# pixelAdapter_l432.net
KiCad netlist of a schematic drawn in EAGLE
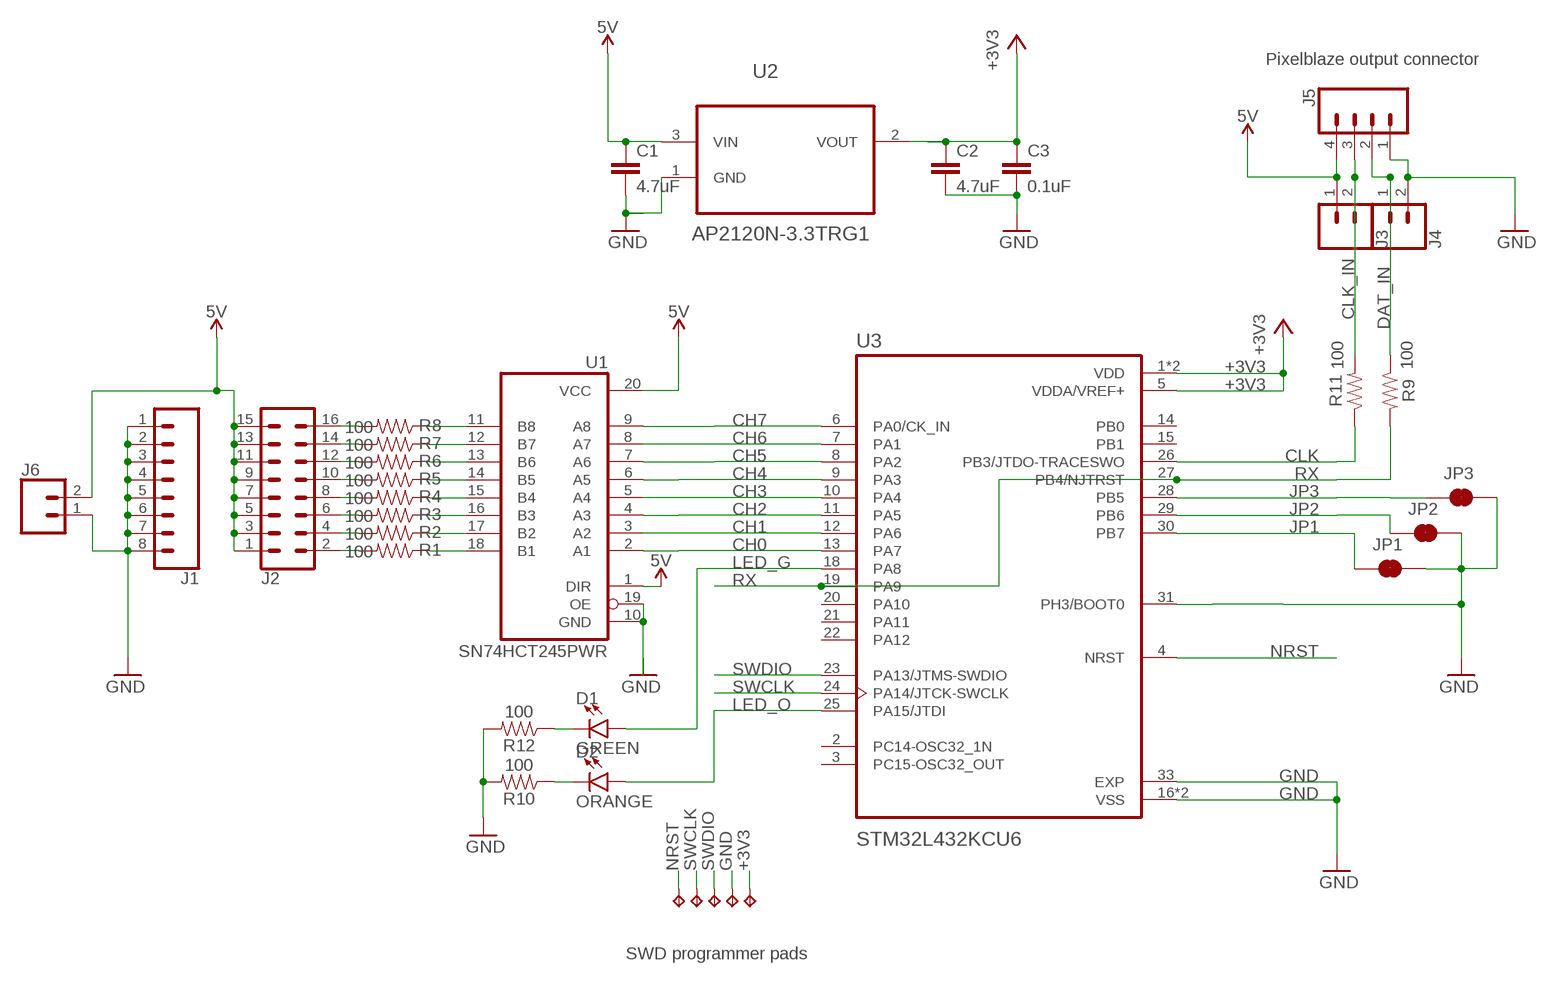
[diagram p0: schematic, sheet 1]

(export (version "E")
  (design (tool "Eeschema 10.0.6"))
  (components
    (comp (ref "C1")
      (value "4.7uF")
      (footprint "eagle-import:0603")
      (libsource (lib "eagle-import") (part "4.7UF0603"))
    )
    (comp (ref "C2")
      (value "4.7uF")
      (footprint "eagle-import:0603")
      (libsource (lib "eagle-import") (part "4.7UF0603"))
    )
    (comp (ref "C3")
      (value "0.1uF")
      (footprint "eagle-import:0603")
      (libsource (lib "eagle-import") (part "0.1UF-0603-25V-(+80/-20%)"))
    )
    (comp (ref "D1")
      (value "GREEN")
      (footprint "eagle-import:LED-0603")
      (libsource (lib "eagle-import") (part "LED0603"))
    )
    (comp (ref "D2")
      (value "ORANGE")
      (footprint "eagle-import:LED-0603")
      (libsource (lib "eagle-import") (part "LED0603"))
    )
    (comp (ref "J1")
      (value "CONN_08NO_SILK_FEMALE_PTH")
      (footprint "eagle-import:1X08_NO_SILK")
      (libsource (lib "eagle-import") (part "CONN_08NO_SILK_FEMALE_PTH"))
    )
    (comp (ref "J2")
      (value "CONN_08X2NOSILK")
      (footprint "eagle-import:2X8-NOSILK")
      (libsource (lib "eagle-import") (part "CONN_08X2NOSILK"))
    )
    (comp (ref "J3")
      (value "CONN_025MM")
      (footprint "eagle-import:SCREWTERMINAL-5MM-2")
      (libsource (lib "eagle-import") (part "bens_CONN_025MM"))
    )
    (comp (ref "J4")
      (value "CONN_025MM")
      (footprint "eagle-import:SCREWTERMINAL-5MM-2")
      (libsource (lib "eagle-import") (part "bens_CONN_025MM"))
    )
    (comp (ref "J5")
      (value "CONN_04LOCK")
      (footprint "eagle-import:1X04_LOCK")
      (libsource (lib "eagle-import") (part "CONN_04LOCK"))
    )
    (comp (ref "J6")
      (value "CONN_02")
      (footprint "eagle-import:1X02")
      (libsource (lib "eagle-import") (part "CONN_02"))
    )
    (comp (ref "JP1")
      (value "JUMPER-SMT_2_NC_TRACE_SILK")
      (footprint "eagle-import:SMT-JUMPER_2_NC_TRACE_SILK")
      (libsource (lib "eagle-import") (part "JUMPER-SMT_2_NC_TRACE_SILK"))
    )
    (comp (ref "JP2")
      (value "JUMPER-SMT_2_NC_TRACE_SILK")
      (footprint "eagle-import:SMT-JUMPER_2_NC_TRACE_SILK")
      (libsource (lib "eagle-import") (part "JUMPER-SMT_2_NC_TRACE_SILK"))
    )
    (comp (ref "JP3")
      (value "JUMPER-SMT_2_NC_TRACE_SILK")
      (footprint "eagle-import:SMT-JUMPER_2_NC_TRACE_SILK")
      (libsource (lib "eagle-import") (part "JUMPER-SMT_2_NC_TRACE_SILK"))
    )
    (comp (ref "R1")
      (value "100")
      (footprint "eagle-import:0603")
      (libsource (lib "eagle-import") (part "100OHM-0603-1/10W-1%"))
    )
    (comp (ref "R2")
      (value "100")
      (footprint "eagle-import:0603")
      (libsource (lib "eagle-import") (part "100OHM-0603-1/10W-1%"))
    )
    (comp (ref "R3")
      (value "100")
      (footprint "eagle-import:0603")
      (libsource (lib "eagle-import") (part "100OHM-0603-1/10W-1%"))
    )
    (comp (ref "R4")
      (value "100")
      (footprint "eagle-import:0603")
      (libsource (lib "eagle-import") (part "100OHM-0603-1/10W-1%"))
    )
    (comp (ref "R5")
      (value "100")
      (footprint "eagle-import:0603")
      (libsource (lib "eagle-import") (part "100OHM-0603-1/10W-1%"))
    )
    (comp (ref "R6")
      (value "100")
      (footprint "eagle-import:0603")
      (libsource (lib "eagle-import") (part "100OHM-0603-1/10W-1%"))
    )
    (comp (ref "R7")
      (value "100")
      (footprint "eagle-import:0603")
      (libsource (lib "eagle-import") (part "100OHM-0603-1/10W-1%"))
    )
    (comp (ref "R8")
      (value "100")
      (footprint "eagle-import:0603")
      (libsource (lib "eagle-import") (part "100OHM-0603-1/10W-1%"))
    )
    (comp (ref "R9")
      (value "100")
      (footprint "eagle-import:0603")
      (libsource (lib "eagle-import") (part "100OHM-0603-1/10W-1%"))
    )
    (comp (ref "R10")
      (value "100")
      (footprint "eagle-import:0603")
      (libsource (lib "eagle-import") (part "100OHM-0603-1/10W-1%"))
    )
    (comp (ref "R11")
      (value "100")
      (footprint "eagle-import:0603")
      (libsource (lib "eagle-import") (part "100OHM-0603-1/10W-1%"))
    )
    (comp (ref "R12")
      (value "100")
      (footprint "eagle-import:0603")
      (libsource (lib "eagle-import") (part "100OHM-0603-1/10W-1%"))
    )
    (comp (ref "TP1")
      (value "TPTP20SQ")
      (footprint "eagle-import:TP20SQ")
      (libsource (lib "eagle-import") (part "TPTP20SQ"))
    )
    (comp (ref "TP2")
      (value "TPTP20SQ")
      (footprint "eagle-import:TP20SQ")
      (libsource (lib "eagle-import") (part "TPTP20SQ"))
    )
    (comp (ref "TP3")
      (value "TPTP20SQ")
      (footprint "eagle-import:TP20SQ")
      (libsource (lib "eagle-import") (part "TPTP20SQ"))
    )
    (comp (ref "TP4")
      (value "TPTP20SQ")
      (footprint "eagle-import:TP20SQ")
      (libsource (lib "eagle-import") (part "TPTP20SQ"))
    )
    (comp (ref "TP5")
      (value "TPTP20SQ")
      (footprint "eagle-import:TP20SQ")
      (libsource (lib "eagle-import") (part "TPTP20SQ"))
    )
    (comp (ref "U1")
      (value "SN74HCT245PWR")
      (footprint "eagle-import:TSSOP20")
      (libsource (lib "eagle-import") (part "74245PW"))
    )
    (comp (ref "U2")
      (value "AP2120N-3.3TRG1")
      (footprint "eagle-import:SOT95P237X112-3N")
      (fields (field (name "MPN") "MCP1700T-3302E/TT"))
      (libsource (lib "eagle-import") (part "MCP1700T-3302E/TT"))
    )
    (comp (ref "U3")
      (value "STM32L432KCU6")
      (footprint "eagle-import:QFN50P500X500X60-33N")
      (fields (field (name "MF") "STMicroelectronics"))
      (libsource (lib "eagle-import") (part "STM32L432KCU6"))
    )
  )
  (nets
    (net (code "1") (name "+3V3") (class "Default")
      (node (ref "C2") (pin "1") (pinfunction "1_1") (pintype "passive"))
      (node (ref "C3") (pin "1") (pinfunction "1_1") (pintype "passive"))
      (node (ref "TP4") (pin "TP") (pinfunction "TP_TP") (pintype "input"))
      (node (ref "U2") (pin "2") (pinfunction "VOUT_2") (pintype "output"))
      (node (ref "U3") (pin "1") (pinfunction "VDD_1") (pintype "power_in"))
      (node (ref "U3") (pin "17") (pinfunction "VDD_17") (pintype "power_in"))
      (node (ref "U3") (pin "5") (pinfunction "VDDA/VREF+_5") (pintype "power_in"))
    )
    (net (code "2") (name "/CH0") (class "Default")
      (node (ref "U1") (pin "2") (pinfunction "A1_2") (pintype "bidirectional"))
      (node (ref "U3") (pin "13") (pinfunction "PA7_13") (pintype "bidirectional"))
    )
    (net (code "3") (name "/CH1") (class "Default")
      (node (ref "U1") (pin "3") (pinfunction "A2_3") (pintype "bidirectional"))
      (node (ref "U3") (pin "12") (pinfunction "PA6_12") (pintype "bidirectional"))
    )
    (net (code "4") (name "/CH2") (class "Default")
      (node (ref "U1") (pin "4") (pinfunction "A3_4") (pintype "bidirectional"))
      (node (ref "U3") (pin "11") (pinfunction "PA5_11") (pintype "bidirectional"))
    )
    (net (code "5") (name "/CH3") (class "Default")
      (node (ref "U1") (pin "5") (pinfunction "A4_5") (pintype "bidirectional"))
      (node (ref "U3") (pin "10") (pinfunction "PA4_10") (pintype "bidirectional"))
    )
    (net (code "6") (name "/CH4") (class "Default")
      (node (ref "U1") (pin "6") (pinfunction "A5_6") (pintype "bidirectional"))
      (node (ref "U3") (pin "9") (pinfunction "PA3_9") (pintype "bidirectional"))
    )
    (net (code "7") (name "/CH5") (class "Default")
      (node (ref "U1") (pin "7") (pinfunction "A6_7") (pintype "bidirectional"))
      (node (ref "U3") (pin "8") (pinfunction "PA2_8") (pintype "bidirectional"))
    )
    (net (code "8") (name "/CH6") (class "Default")
      (node (ref "U1") (pin "8") (pinfunction "A7_8") (pintype "bidirectional"))
      (node (ref "U3") (pin "7") (pinfunction "PA1_7") (pintype "bidirectional"))
    )
    (net (code "9") (name "/CH7") (class "Default")
      (node (ref "U1") (pin "9") (pinfunction "A8_9") (pintype "bidirectional"))
      (node (ref "U3") (pin "6") (pinfunction "PA0/CK_IN_6") (pintype "bidirectional"))
    )
    (net (code "10") (name "/CLK") (class "Default")
      (node (ref "R11") (pin "1") (pinfunction "1_1") (pintype "passive"))
      (node (ref "U3") (pin "26") (pinfunction "PB3/JTDO-TRACESWO_26") (pintype "bidirectional"))
    )
    (net (code "11") (name "/CLK_IN") (class "Default")
      (node (ref "J3") (pin "2") (pinfunction "2_2") (pintype "passive"))
      (node (ref "J5") (pin "3") (pinfunction "3_3") (pintype "passive"))
      (node (ref "R11") (pin "2") (pinfunction "2_2") (pintype "passive"))
    )
    (net (code "12") (name "/DAT_IN") (class "Default")
      (node (ref "J4") (pin "1") (pinfunction "1_1") (pintype "passive"))
      (node (ref "J5") (pin "2") (pinfunction "2_2") (pintype "passive"))
      (node (ref "R9") (pin "1") (pinfunction "1_1") (pintype "passive"))
    )
    (net (code "13") (name "/JP1") (class "Default")
      (node (ref "JP1") (pin "1") (pinfunction "1_1") (pintype "passive"))
      (node (ref "U3") (pin "30") (pinfunction "PB7_30") (pintype "bidirectional"))
    )
    (net (code "14") (name "/JP2") (class "Default")
      (node (ref "JP2") (pin "1") (pinfunction "1_1") (pintype "passive"))
      (node (ref "U3") (pin "29") (pinfunction "PB6_29") (pintype "bidirectional"))
    )
    (net (code "15") (name "/JP3") (class "Default")
      (node (ref "JP3") (pin "2") (pinfunction "2_2") (pintype "passive"))
      (node (ref "U3") (pin "28") (pinfunction "PB5_28") (pintype "bidirectional"))
    )
    (net (code "16") (name "/LED_G") (class "Default")
      (node (ref "D1") (pin "A") (pinfunction "A_A") (pintype "passive"))
      (node (ref "U3") (pin "18") (pinfunction "PA8_18") (pintype "bidirectional"))
    )
    (net (code "17") (name "/LED_O") (class "Default")
      (node (ref "D2") (pin "A") (pinfunction "A_A") (pintype "passive"))
      (node (ref "U3") (pin "25") (pinfunction "PA15/JTDI_25") (pintype "bidirectional"))
    )
    (net (code "18") (name "/NRST") (class "Default")
      (node (ref "TP5") (pin "TP") (pinfunction "TP_TP") (pintype "input"))
      (node (ref "U3") (pin "4") (pinfunction "NRST_4") (pintype "bidirectional"))
    )
    (net (code "19") (name "/RX") (class "Default")
      (node (ref "R9") (pin "2") (pinfunction "2_2") (pintype "passive"))
      (node (ref "U3") (pin "19") (pinfunction "PA9_19") (pintype "bidirectional"))
      (node (ref "U3") (pin "27") (pinfunction "PB4/NJTRST_27") (pintype "bidirectional"))
    )
    (net (code "20") (name "/SWCLK") (class "Default")
      (node (ref "TP1") (pin "TP") (pinfunction "TP_TP") (pintype "input"))
      (node (ref "U3") (pin "24") (pinfunction "PA14/JTCK-SWCLK_24") (pintype "bidirectional"))
    )
    (net (code "21") (name "/SWDIO") (class "Default")
      (node (ref "TP2") (pin "TP") (pinfunction "TP_TP") (pintype "input"))
      (node (ref "U3") (pin "23") (pinfunction "PA13/JTMS-SWDIO_23") (pintype "bidirectional"))
    )
    (net (code "22") (name "5V") (class "Default")
      (node (ref "C1") (pin "1") (pinfunction "1_1") (pintype "passive"))
      (node (ref "J2") (pin "1") (pinfunction "1_1") (pintype "passive"))
      (node (ref "J2") (pin "11") (pinfunction "11_11") (pintype "passive"))
      (node (ref "J2") (pin "13") (pinfunction "13_13") (pintype "passive"))
      (node (ref "J2") (pin "15") (pinfunction "15_15") (pintype "passive"))
      (node (ref "J2") (pin "3") (pinfunction "3_3") (pintype "passive"))
      (node (ref "J2") (pin "5") (pinfunction "5_5") (pintype "passive"))
      (node (ref "J2") (pin "7") (pinfunction "7_7") (pintype "passive"))
      (node (ref "J2") (pin "9") (pinfunction "9_9") (pintype "passive"))
      (node (ref "J3") (pin "1") (pinfunction "1_1") (pintype "passive"))
      (node (ref "J5") (pin "4") (pinfunction "4_4") (pintype "passive"))
      (node (ref "J6") (pin "2") (pinfunction "2_2") (pintype "passive"))
      (node (ref "U1") (pin "1") (pinfunction "DIR_1") (pintype "input"))
      (node (ref "U1") (pin "20") (pinfunction "VCC_20") (pintype "bidirectional"))
      (node (ref "U2") (pin "3") (pinfunction "VIN_3") (pintype "input"))
    )
    (net (code "23") (name "GND") (class "Default")
      (node (ref "C1") (pin "2") (pinfunction "2_2") (pintype "passive"))
      (node (ref "C2") (pin "2") (pinfunction "2_2") (pintype "passive"))
      (node (ref "C3") (pin "2") (pinfunction "2_2") (pintype "passive"))
      (node (ref "J1") (pin "1") (pinfunction "1_1") (pintype "passive"))
      (node (ref "J1") (pin "2") (pinfunction "2_2") (pintype "passive"))
      (node (ref "J1") (pin "3") (pinfunction "3_3") (pintype "passive"))
      (node (ref "J1") (pin "4") (pinfunction "4_4") (pintype "passive"))
      (node (ref "J1") (pin "5") (pinfunction "5_5") (pintype "passive"))
      (node (ref "J1") (pin "6") (pinfunction "6_6") (pintype "passive"))
      (node (ref "J1") (pin "7") (pinfunction "7_7") (pintype "passive"))
      (node (ref "J1") (pin "8") (pinfunction "8_8") (pintype "passive"))
      (node (ref "J4") (pin "2") (pinfunction "2_2") (pintype "passive"))
      (node (ref "J5") (pin "1") (pinfunction "1_1") (pintype "passive"))
      (node (ref "J6") (pin "1") (pinfunction "1_1") (pintype "passive"))
      (node (ref "JP1") (pin "2") (pinfunction "2_2") (pintype "passive"))
      (node (ref "JP2") (pin "2") (pinfunction "2_2") (pintype "passive"))
      (node (ref "JP3") (pin "1") (pinfunction "1_1") (pintype "passive"))
      (node (ref "R10") (pin "2") (pinfunction "2_2") (pintype "passive"))
      (node (ref "R12") (pin "2") (pinfunction "2_2") (pintype "passive"))
      (node (ref "TP3") (pin "TP") (pinfunction "TP_TP") (pintype "input"))
      (node (ref "U1") (pin "10") (pinfunction "GND_10") (pintype "bidirectional"))
      (node (ref "U1") (pin "19") (pinfunction "OE_19") (pintype "input"))
      (node (ref "U2") (pin "1") (pinfunction "GND_1") (pintype "passive"))
      (node (ref "U3") (pin "16") (pinfunction "VSS_16") (pintype "power_in"))
      (node (ref "U3") (pin "31") (pinfunction "PH3/BOOT0_31") (pintype "bidirectional"))
      (node (ref "U3") (pin "32") (pinfunction "VSS_32") (pintype "power_in"))
      (node (ref "U3") (pin "33") (pinfunction "EXP_33") (pintype "power_in"))
    )
    (net (code "24") (name "Net-(D1-PadC)") (class "Default")
      (node (ref "D1") (pin "C") (pinfunction "C_C") (pintype "passive"))
      (node (ref "R12") (pin "1") (pinfunction "1_1") (pintype "passive"))
    )
    (net (code "25") (name "Net-(D2-PadC)") (class "Default")
      (node (ref "D2") (pin "C") (pinfunction "C_C") (pintype "passive"))
      (node (ref "R10") (pin "1") (pinfunction "1_1") (pintype "passive"))
    )
    (net (code "26") (name "Net-(J2-Pad2)") (class "Default")
      (node (ref "J2") (pin "2") (pinfunction "2_2") (pintype "passive"))
      (node (ref "R1") (pin "2") (pinfunction "2_2") (pintype "passive"))
    )
    (net (code "27") (name "Net-(J2-Pad4)") (class "Default")
      (node (ref "J2") (pin "4") (pinfunction "4_4") (pintype "passive"))
      (node (ref "R2") (pin "2") (pinfunction "2_2") (pintype "passive"))
    )
    (net (code "28") (name "Net-(J2-Pad6)") (class "Default")
      (node (ref "J2") (pin "6") (pinfunction "6_6") (pintype "passive"))
      (node (ref "R3") (pin "2") (pinfunction "2_2") (pintype "passive"))
    )
    (net (code "29") (name "Net-(J2-Pad8)") (class "Default")
      (node (ref "J2") (pin "8") (pinfunction "8_8") (pintype "passive"))
      (node (ref "R4") (pin "2") (pinfunction "2_2") (pintype "passive"))
    )
    (net (code "30") (name "Net-(J2-Pad10)") (class "Default")
      (node (ref "J2") (pin "10") (pinfunction "10_10") (pintype "passive"))
      (node (ref "R5") (pin "2") (pinfunction "2_2") (pintype "passive"))
    )
    (net (code "31") (name "Net-(J2-Pad12)") (class "Default")
      (node (ref "J2") (pin "12") (pinfunction "12_12") (pintype "passive"))
      (node (ref "R6") (pin "2") (pinfunction "2_2") (pintype "passive"))
    )
    (net (code "32") (name "Net-(J2-Pad14)") (class "Default")
      (node (ref "J2") (pin "14") (pinfunction "14_14") (pintype "passive"))
      (node (ref "R7") (pin "2") (pinfunction "2_2") (pintype "passive"))
    )
    (net (code "33") (name "Net-(J2-Pad16)") (class "Default")
      (node (ref "J2") (pin "16") (pinfunction "16_16") (pintype "passive"))
      (node (ref "R8") (pin "2") (pinfunction "2_2") (pintype "passive"))
    )
    (net (code "34") (name "Net-(U1-B1)") (class "Default")
      (node (ref "R1") (pin "1") (pinfunction "1_1") (pintype "passive"))
      (node (ref "U1") (pin "18") (pinfunction "B1_18") (pintype "bidirectional"))
    )
    (net (code "35") (name "Net-(U1-B2)") (class "Default")
      (node (ref "R2") (pin "1") (pinfunction "1_1") (pintype "passive"))
      (node (ref "U1") (pin "17") (pinfunction "B2_17") (pintype "bidirectional"))
    )
    (net (code "36") (name "Net-(U1-B3)") (class "Default")
      (node (ref "R3") (pin "1") (pinfunction "1_1") (pintype "passive"))
      (node (ref "U1") (pin "16") (pinfunction "B3_16") (pintype "bidirectional"))
    )
    (net (code "37") (name "Net-(U1-B4)") (class "Default")
      (node (ref "R4") (pin "1") (pinfunction "1_1") (pintype "passive"))
      (node (ref "U1") (pin "15") (pinfunction "B4_15") (pintype "bidirectional"))
    )
    (net (code "38") (name "Net-(U1-B5)") (class "Default")
      (node (ref "R5") (pin "1") (pinfunction "1_1") (pintype "passive"))
      (node (ref "U1") (pin "14") (pinfunction "B5_14") (pintype "bidirectional"))
    )
    (net (code "39") (name "Net-(U1-B6)") (class "Default")
      (node (ref "R6") (pin "1") (pinfunction "1_1") (pintype "passive"))
      (node (ref "U1") (pin "13") (pinfunction "B6_13") (pintype "bidirectional"))
    )
    (net (code "40") (name "Net-(U1-B7)") (class "Default")
      (node (ref "R7") (pin "1") (pinfunction "1_1") (pintype "passive"))
      (node (ref "U1") (pin "12") (pinfunction "B7_12") (pintype "bidirectional"))
    )
    (net (code "41") (name "Net-(U1-B8)") (class "Default")
      (node (ref "R8") (pin "1") (pinfunction "1_1") (pintype "passive"))
      (node (ref "U1") (pin "11") (pinfunction "B8_11") (pintype "bidirectional"))
    )
    (net (code "42") (name "unconnected-(U3-PA10-Pad20)") (class "Default")
      (node (ref "U3") (pin "20") (pinfunction "PA10_20") (pintype "bidirectional"))
    )
    (net (code "43") (name "unconnected-(U3-PA11-Pad21)") (class "Default")
      (node (ref "U3") (pin "21") (pinfunction "PA11_21") (pintype "bidirectional"))
    )
    (net (code "44") (name "unconnected-(U3-PA12-Pad22)") (class "Default")
      (node (ref "U3") (pin "22") (pinfunction "PA12_22") (pintype "bidirectional"))
    )
    (net (code "45") (name "unconnected-(U3-PB0-Pad14)") (class "Default")
      (node (ref "U3") (pin "14") (pinfunction "PB0_14") (pintype "bidirectional"))
    )
    (net (code "46") (name "unconnected-(U3-PB1-Pad15)") (class "Default")
      (node (ref "U3") (pin "15") (pinfunction "PB1_15") (pintype "bidirectional"))
    )
    (net (code "47") (name "unconnected-(U3-PC14-OSC32_1N-Pad2)") (class "Default")
      (node (ref "U3") (pin "2") (pinfunction "PC14-OSC32_1N_2") (pintype "bidirectional"))
    )
    (net (code "48") (name "unconnected-(U3-PC15-OSC32_OUT-Pad3)") (class "Default")
      (node (ref "U3") (pin "3") (pinfunction "PC15-OSC32_OUT_3") (pintype "bidirectional"))
    )
  )
)
